# GREEN_SCH.net
KiCad netlist of a schematic drawn in Altium Designer
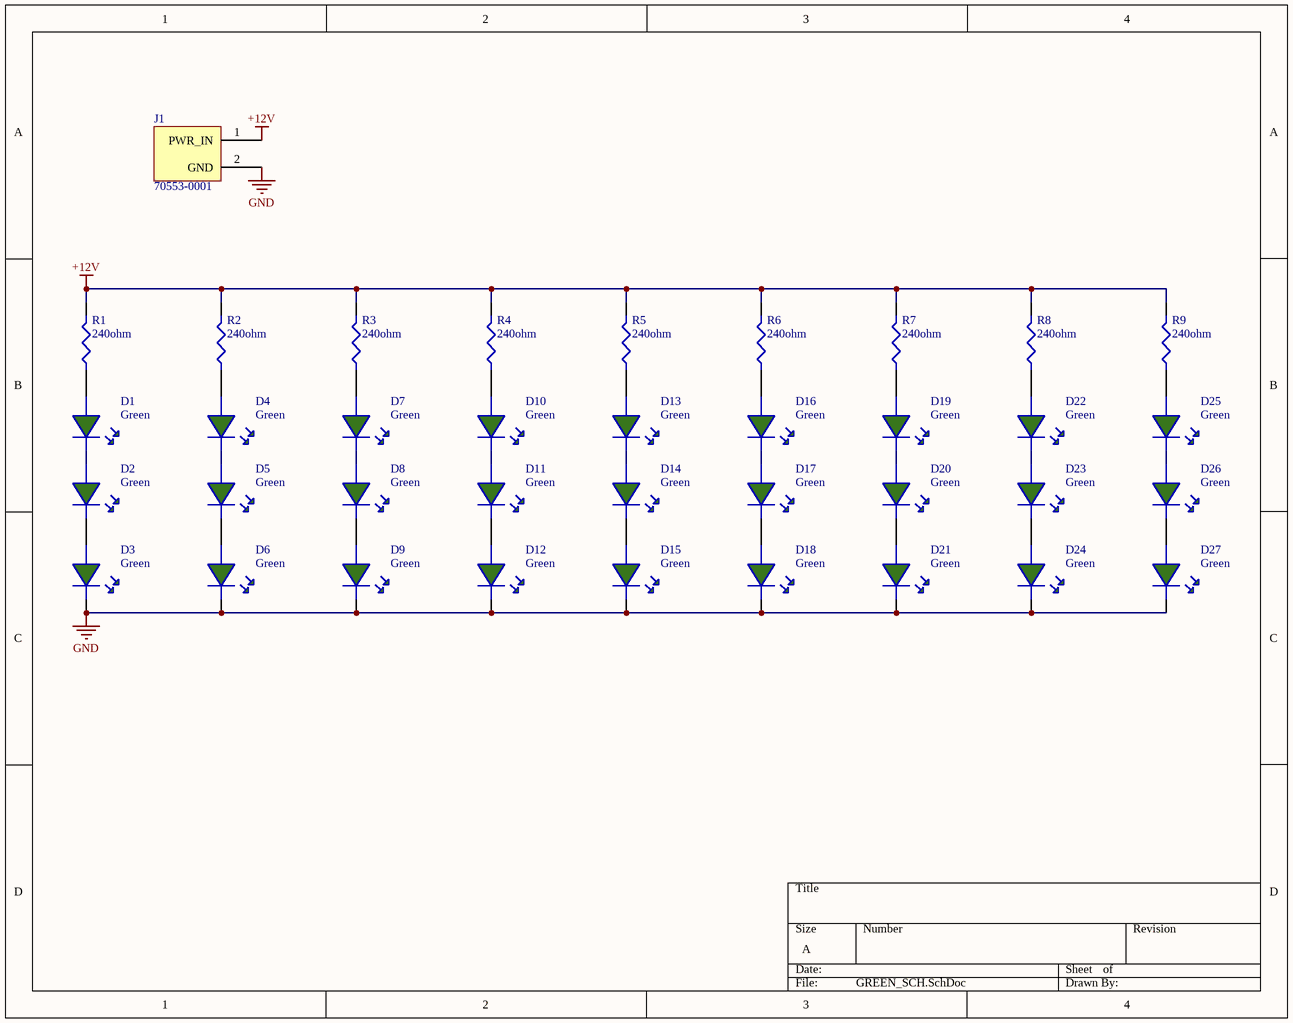
[diagram p0: GREEN_SCH.SchDoc]

(export (version "E")
  (design (tool "Eeschema 10.0.6"))
  (components
    (comp (ref "D1")
      (value "Green")
      (footprint "GREEN_LED")
      (description "LED GREEN CLEAR 0603 SMD")
      (fields (field (name "MANUFACTURER") "Inolux") (field (name "MANUFACTURER PART NUMBER") "IN-S63AT5G"))
      (libsource (lib "symbols") (part "IN-S63AT5G"))
    )
    (comp (ref "D2")
      (value "Green")
      (footprint "GREEN_LED")
      (description "LED GREEN CLEAR 0603 SMD")
      (fields (field (name "MANUFACTURER") "Inolux") (field (name "MANUFACTURER PART NUMBER") "IN-S63AT5G"))
      (libsource (lib "symbols") (part "IN-S63AT5G"))
    )
    (comp (ref "D3")
      (value "Green")
      (footprint "GREEN_LED")
      (description "LED GREEN CLEAR 0603 SMD")
      (fields (field (name "MANUFACTURER") "Inolux") (field (name "MANUFACTURER PART NUMBER") "IN-S63AT5G"))
      (libsource (lib "symbols") (part "IN-S63AT5G"))
    )
    (comp (ref "D4")
      (value "Green")
      (footprint "GREEN_LED")
      (description "LED GREEN CLEAR 0603 SMD")
      (fields (field (name "MANUFACTURER") "Inolux") (field (name "MANUFACTURER PART NUMBER") "IN-S63AT5G"))
      (libsource (lib "symbols") (part "IN-S63AT5G"))
    )
    (comp (ref "D5")
      (value "Green")
      (footprint "GREEN_LED")
      (description "LED GREEN CLEAR 0603 SMD")
      (fields (field (name "MANUFACTURER") "Inolux") (field (name "MANUFACTURER PART NUMBER") "IN-S63AT5G"))
      (libsource (lib "symbols") (part "IN-S63AT5G"))
    )
    (comp (ref "D6")
      (value "Green")
      (footprint "GREEN_LED")
      (description "LED GREEN CLEAR 0603 SMD")
      (fields (field (name "MANUFACTURER") "Inolux") (field (name "MANUFACTURER PART NUMBER") "IN-S63AT5G"))
      (libsource (lib "symbols") (part "IN-S63AT5G"))
    )
    (comp (ref "D7")
      (value "Green")
      (footprint "GREEN_LED")
      (description "LED GREEN CLEAR 0603 SMD")
      (fields (field (name "MANUFACTURER") "Inolux") (field (name "MANUFACTURER PART NUMBER") "IN-S63AT5G"))
      (libsource (lib "symbols") (part "IN-S63AT5G"))
    )
    (comp (ref "D8")
      (value "Green")
      (footprint "GREEN_LED")
      (description "LED GREEN CLEAR 0603 SMD")
      (fields (field (name "MANUFACTURER") "Inolux") (field (name "MANUFACTURER PART NUMBER") "IN-S63AT5G"))
      (libsource (lib "symbols") (part "IN-S63AT5G"))
    )
    (comp (ref "D9")
      (value "Green")
      (footprint "GREEN_LED")
      (description "LED GREEN CLEAR 0603 SMD")
      (fields (field (name "MANUFACTURER") "Inolux") (field (name "MANUFACTURER PART NUMBER") "IN-S63AT5G"))
      (libsource (lib "symbols") (part "IN-S63AT5G"))
    )
    (comp (ref "D10")
      (value "Green")
      (footprint "GREEN_LED")
      (description "LED GREEN CLEAR 0603 SMD")
      (fields (field (name "MANUFACTURER") "Inolux") (field (name "MANUFACTURER PART NUMBER") "IN-S63AT5G"))
      (libsource (lib "symbols") (part "IN-S63AT5G"))
    )
    (comp (ref "D11")
      (value "Green")
      (footprint "GREEN_LED")
      (description "LED GREEN CLEAR 0603 SMD")
      (fields (field (name "MANUFACTURER") "Inolux") (field (name "MANUFACTURER PART NUMBER") "IN-S63AT5G"))
      (libsource (lib "symbols") (part "IN-S63AT5G"))
    )
    (comp (ref "D12")
      (value "Green")
      (footprint "GREEN_LED")
      (description "LED GREEN CLEAR 0603 SMD")
      (fields (field (name "MANUFACTURER") "Inolux") (field (name "MANUFACTURER PART NUMBER") "IN-S63AT5G"))
      (libsource (lib "symbols") (part "IN-S63AT5G"))
    )
    (comp (ref "D13")
      (value "Green")
      (footprint "GREEN_LED")
      (description "LED GREEN CLEAR 0603 SMD")
      (fields (field (name "MANUFACTURER") "Inolux") (field (name "MANUFACTURER PART NUMBER") "IN-S63AT5G"))
      (libsource (lib "symbols") (part "IN-S63AT5G"))
    )
    (comp (ref "D14")
      (value "Green")
      (footprint "GREEN_LED")
      (description "LED GREEN CLEAR 0603 SMD")
      (fields (field (name "MANUFACTURER") "Inolux") (field (name "MANUFACTURER PART NUMBER") "IN-S63AT5G"))
      (libsource (lib "symbols") (part "IN-S63AT5G"))
    )
    (comp (ref "D15")
      (value "Green")
      (footprint "GREEN_LED")
      (description "LED GREEN CLEAR 0603 SMD")
      (fields (field (name "MANUFACTURER") "Inolux") (field (name "MANUFACTURER PART NUMBER") "IN-S63AT5G"))
      (libsource (lib "symbols") (part "IN-S63AT5G"))
    )
    (comp (ref "D16")
      (value "Green")
      (footprint "GREEN_LED")
      (description "LED GREEN CLEAR 0603 SMD")
      (fields (field (name "MANUFACTURER") "Inolux") (field (name "MANUFACTURER PART NUMBER") "IN-S63AT5G"))
      (libsource (lib "symbols") (part "IN-S63AT5G"))
    )
    (comp (ref "D17")
      (value "Green")
      (footprint "GREEN_LED")
      (description "LED GREEN CLEAR 0603 SMD")
      (fields (field (name "MANUFACTURER") "Inolux") (field (name "MANUFACTURER PART NUMBER") "IN-S63AT5G"))
      (libsource (lib "symbols") (part "IN-S63AT5G"))
    )
    (comp (ref "D18")
      (value "Green")
      (footprint "GREEN_LED")
      (description "LED GREEN CLEAR 0603 SMD")
      (fields (field (name "MANUFACTURER") "Inolux") (field (name "MANUFACTURER PART NUMBER") "IN-S63AT5G"))
      (libsource (lib "symbols") (part "IN-S63AT5G"))
    )
    (comp (ref "D19")
      (value "Green")
      (footprint "GREEN_LED")
      (description "LED GREEN CLEAR 0603 SMD")
      (fields (field (name "MANUFACTURER") "Inolux") (field (name "MANUFACTURER PART NUMBER") "IN-S63AT5G"))
      (libsource (lib "symbols") (part "IN-S63AT5G"))
    )
    (comp (ref "D20")
      (value "Green")
      (footprint "GREEN_LED")
      (description "LED GREEN CLEAR 0603 SMD")
      (fields (field (name "MANUFACTURER") "Inolux") (field (name "MANUFACTURER PART NUMBER") "IN-S63AT5G"))
      (libsource (lib "symbols") (part "IN-S63AT5G"))
    )
    (comp (ref "D21")
      (value "Green")
      (footprint "GREEN_LED")
      (description "LED GREEN CLEAR 0603 SMD")
      (fields (field (name "MANUFACTURER") "Inolux") (field (name "MANUFACTURER PART NUMBER") "IN-S63AT5G"))
      (libsource (lib "symbols") (part "IN-S63AT5G"))
    )
    (comp (ref "D22")
      (value "Green")
      (footprint "GREEN_LED")
      (description "LED GREEN CLEAR 0603 SMD")
      (fields (field (name "MANUFACTURER") "Inolux") (field (name "MANUFACTURER PART NUMBER") "IN-S63AT5G"))
      (libsource (lib "symbols") (part "IN-S63AT5G"))
    )
    (comp (ref "D23")
      (value "Green")
      (footprint "GREEN_LED")
      (description "LED GREEN CLEAR 0603 SMD")
      (fields (field (name "MANUFACTURER") "Inolux") (field (name "MANUFACTURER PART NUMBER") "IN-S63AT5G"))
      (libsource (lib "symbols") (part "IN-S63AT5G"))
    )
    (comp (ref "D24")
      (value "Green")
      (footprint "GREEN_LED")
      (description "LED GREEN CLEAR 0603 SMD")
      (fields (field (name "MANUFACTURER") "Inolux") (field (name "MANUFACTURER PART NUMBER") "IN-S63AT5G"))
      (libsource (lib "symbols") (part "IN-S63AT5G"))
    )
    (comp (ref "D25")
      (value "Green")
      (footprint "GREEN_LED")
      (description "LED GREEN CLEAR 0603 SMD")
      (fields (field (name "MANUFACTURER") "Inolux") (field (name "MANUFACTURER PART NUMBER") "IN-S63AT5G"))
      (libsource (lib "symbols") (part "IN-S63AT5G"))
    )
    (comp (ref "D26")
      (value "Green")
      (footprint "GREEN_LED")
      (description "LED GREEN CLEAR 0603 SMD")
      (fields (field (name "MANUFACTURER") "Inolux") (field (name "MANUFACTURER PART NUMBER") "IN-S63AT5G"))
      (libsource (lib "symbols") (part "IN-S63AT5G"))
    )
    (comp (ref "D27")
      (value "Green")
      (footprint "GREEN_LED")
      (description "LED GREEN CLEAR 0603 SMD")
      (fields (field (name "MANUFACTURER") "Inolux") (field (name "MANUFACTURER PART NUMBER") "IN-S63AT5G"))
      (libsource (lib "symbols") (part "IN-S63AT5G"))
    )
    (comp (ref "J1")
      (value "70553-0001")
      (footprint "CONNECTOR")
      (description "Headers & Wire Housings R/A HDR 2P low profile single")
      (fields (field (name "MANUFACTURER") "Molex"))
      (libsource (lib "symbols") (part "70553-0001"))
    )
    (comp (ref "R1")
      (value "240ohm")
      (footprint "RESISTOR_0805")
      (description "RES SMD 240 OHM 0.1% 1/8W 0805")
      (fields
        (field (name "MANUFACTURER") "Panasonic")
        (field (name "MANUFACTURER PART NUMBER") "ERA-6AEB241V")
      )
      (libsource (lib "symbols") (part "ERA-6AEB241V"))
    )
    (comp (ref "R2")
      (value "240ohm")
      (footprint "RESISTOR_0805")
      (description "RES SMD 240 OHM 0.1% 1/8W 0805")
      (fields
        (field (name "MANUFACTURER") "Panasonic")
        (field (name "MANUFACTURER PART NUMBER") "ERA-6AEB241V")
      )
      (libsource (lib "symbols") (part "ERA-6AEB241V"))
    )
    (comp (ref "R3")
      (value "240ohm")
      (footprint "RESISTOR_0805")
      (description "RES SMD 240 OHM 0.1% 1/8W 0805")
      (fields
        (field (name "MANUFACTURER") "Panasonic")
        (field (name "MANUFACTURER PART NUMBER") "ERA-6AEB241V")
      )
      (libsource (lib "symbols") (part "ERA-6AEB241V"))
    )
    (comp (ref "R4")
      (value "240ohm")
      (footprint "RESISTOR_0805")
      (description "RES SMD 240 OHM 0.1% 1/8W 0805")
      (fields
        (field (name "MANUFACTURER") "Panasonic")
        (field (name "MANUFACTURER PART NUMBER") "ERA-6AEB241V")
      )
      (libsource (lib "symbols") (part "ERA-6AEB241V"))
    )
    (comp (ref "R5")
      (value "240ohm")
      (footprint "RESISTOR_0805")
      (description "RES SMD 240 OHM 0.1% 1/8W 0805")
      (fields
        (field (name "MANUFACTURER") "Panasonic")
        (field (name "MANUFACTURER PART NUMBER") "ERA-6AEB241V")
      )
      (libsource (lib "symbols") (part "ERA-6AEB241V"))
    )
    (comp (ref "R6")
      (value "240ohm")
      (footprint "RESISTOR_0805")
      (description "RES SMD 240 OHM 0.1% 1/8W 0805")
      (fields
        (field (name "MANUFACTURER") "Panasonic")
        (field (name "MANUFACTURER PART NUMBER") "ERA-6AEB241V")
      )
      (libsource (lib "symbols") (part "ERA-6AEB241V"))
    )
    (comp (ref "R7")
      (value "240ohm")
      (footprint "RESISTOR_0805")
      (description "RES SMD 240 OHM 0.1% 1/8W 0805")
      (fields
        (field (name "MANUFACTURER") "Panasonic")
        (field (name "MANUFACTURER PART NUMBER") "ERA-6AEB241V")
      )
      (libsource (lib "symbols") (part "ERA-6AEB241V"))
    )
    (comp (ref "R8")
      (value "240ohm")
      (footprint "RESISTOR_0805")
      (description "RES SMD 240 OHM 0.1% 1/8W 0805")
      (fields
        (field (name "MANUFACTURER") "Panasonic")
        (field (name "MANUFACTURER PART NUMBER") "ERA-6AEB241V")
      )
      (libsource (lib "symbols") (part "ERA-6AEB241V"))
    )
    (comp (ref "R9")
      (value "240ohm")
      (footprint "RESISTOR_0805")
      (description "RES SMD 240 OHM 0.1% 1/8W 0805")
      (fields
        (field (name "MANUFACTURER") "Panasonic")
        (field (name "MANUFACTURER PART NUMBER") "ERA-6AEB241V")
      )
      (libsource (lib "symbols") (part "ERA-6AEB241V"))
    )
  )
  (nets
    (net (code "1") (name "+12V") (class "Default")
      (node (ref "J1") (pin "1") (pinfunction "PWR_IN_1") (pintype "passive"))
      (node (ref "R1") (pin "2") (pinfunction "2_2") (pintype "passive"))
      (node (ref "R2") (pin "2") (pinfunction "2_2") (pintype "passive"))
      (node (ref "R3") (pin "2") (pinfunction "2_2") (pintype "passive"))
      (node (ref "R4") (pin "2") (pinfunction "2_2") (pintype "passive"))
      (node (ref "R5") (pin "2") (pinfunction "2_2") (pintype "passive"))
      (node (ref "R6") (pin "2") (pinfunction "2_2") (pintype "passive"))
      (node (ref "R7") (pin "2") (pinfunction "2_2") (pintype "passive"))
      (node (ref "R8") (pin "2") (pinfunction "2_2") (pintype "passive"))
      (node (ref "R9") (pin "2") (pinfunction "2_2") (pintype "passive"))
    )
    (net (code "2") (name "GND") (class "Default")
      (node (ref "D12") (pin "2") (pinfunction "2_2") (pintype "passive"))
      (node (ref "D15") (pin "2") (pinfunction "2_2") (pintype "passive"))
      (node (ref "D18") (pin "2") (pinfunction "2_2") (pintype "passive"))
      (node (ref "D21") (pin "2") (pinfunction "2_2") (pintype "passive"))
      (node (ref "D24") (pin "2") (pinfunction "2_2") (pintype "passive"))
      (node (ref "D27") (pin "2") (pinfunction "2_2") (pintype "passive"))
      (node (ref "D3") (pin "2") (pinfunction "2_2") (pintype "passive"))
      (node (ref "D6") (pin "2") (pinfunction "2_2") (pintype "passive"))
      (node (ref "D9") (pin "2") (pinfunction "2_2") (pintype "passive"))
      (node (ref "J1") (pin "2") (pinfunction "GND_2") (pintype "passive"))
    )
    (net (code "3") (name "Net-(D1-Pad1)") (class "Default")
      (node (ref "D1") (pin "1") (pinfunction "1_1") (pintype "passive"))
      (node (ref "R1") (pin "1") (pinfunction "1_1") (pintype "passive"))
    )
    (net (code "4") (name "Net-(D1-Pad2)") (class "Default")
      (node (ref "D1") (pin "2") (pinfunction "2_2") (pintype "passive"))
      (node (ref "D2") (pin "1") (pinfunction "1_1") (pintype "passive"))
    )
    (net (code "5") (name "Net-(D2-Pad2)") (class "Default")
      (node (ref "D2") (pin "2") (pinfunction "2_2") (pintype "passive"))
      (node (ref "D3") (pin "1") (pinfunction "1_1") (pintype "passive"))
    )
    (net (code "6") (name "Net-(D4-Pad1)") (class "Default")
      (node (ref "D4") (pin "1") (pinfunction "1_1") (pintype "passive"))
      (node (ref "R2") (pin "1") (pinfunction "1_1") (pintype "passive"))
    )
    (net (code "7") (name "Net-(D4-Pad2)") (class "Default")
      (node (ref "D4") (pin "2") (pinfunction "2_2") (pintype "passive"))
      (node (ref "D5") (pin "1") (pinfunction "1_1") (pintype "passive"))
    )
    (net (code "8") (name "Net-(D5-Pad2)") (class "Default")
      (node (ref "D5") (pin "2") (pinfunction "2_2") (pintype "passive"))
      (node (ref "D6") (pin "1") (pinfunction "1_1") (pintype "passive"))
    )
    (net (code "9") (name "Net-(D7-Pad1)") (class "Default")
      (node (ref "D7") (pin "1") (pinfunction "1_1") (pintype "passive"))
      (node (ref "R3") (pin "1") (pinfunction "1_1") (pintype "passive"))
    )
    (net (code "10") (name "Net-(D7-Pad2)") (class "Default")
      (node (ref "D7") (pin "2") (pinfunction "2_2") (pintype "passive"))
      (node (ref "D8") (pin "1") (pinfunction "1_1") (pintype "passive"))
    )
    (net (code "11") (name "Net-(D8-Pad2)") (class "Default")
      (node (ref "D8") (pin "2") (pinfunction "2_2") (pintype "passive"))
      (node (ref "D9") (pin "1") (pinfunction "1_1") (pintype "passive"))
    )
    (net (code "12") (name "Net-(D10-Pad1)") (class "Default")
      (node (ref "D10") (pin "1") (pinfunction "1_1") (pintype "passive"))
      (node (ref "R4") (pin "1") (pinfunction "1_1") (pintype "passive"))
    )
    (net (code "13") (name "Net-(D10-Pad2)") (class "Default")
      (node (ref "D10") (pin "2") (pinfunction "2_2") (pintype "passive"))
      (node (ref "D11") (pin "1") (pinfunction "1_1") (pintype "passive"))
    )
    (net (code "14") (name "Net-(D11-Pad2)") (class "Default")
      (node (ref "D11") (pin "2") (pinfunction "2_2") (pintype "passive"))
      (node (ref "D12") (pin "1") (pinfunction "1_1") (pintype "passive"))
    )
    (net (code "15") (name "Net-(D13-Pad1)") (class "Default")
      (node (ref "D13") (pin "1") (pinfunction "1_1") (pintype "passive"))
      (node (ref "R5") (pin "1") (pinfunction "1_1") (pintype "passive"))
    )
    (net (code "16") (name "Net-(D13-Pad2)") (class "Default")
      (node (ref "D13") (pin "2") (pinfunction "2_2") (pintype "passive"))
      (node (ref "D14") (pin "1") (pinfunction "1_1") (pintype "passive"))
    )
    (net (code "17") (name "Net-(D14-Pad2)") (class "Default")
      (node (ref "D14") (pin "2") (pinfunction "2_2") (pintype "passive"))
      (node (ref "D15") (pin "1") (pinfunction "1_1") (pintype "passive"))
    )
    (net (code "18") (name "Net-(D16-Pad1)") (class "Default")
      (node (ref "D16") (pin "1") (pinfunction "1_1") (pintype "passive"))
      (node (ref "R6") (pin "1") (pinfunction "1_1") (pintype "passive"))
    )
    (net (code "19") (name "Net-(D16-Pad2)") (class "Default")
      (node (ref "D16") (pin "2") (pinfunction "2_2") (pintype "passive"))
      (node (ref "D17") (pin "1") (pinfunction "1_1") (pintype "passive"))
    )
    (net (code "20") (name "Net-(D17-Pad2)") (class "Default")
      (node (ref "D17") (pin "2") (pinfunction "2_2") (pintype "passive"))
      (node (ref "D18") (pin "1") (pinfunction "1_1") (pintype "passive"))
    )
    (net (code "21") (name "Net-(D19-Pad1)") (class "Default")
      (node (ref "D19") (pin "1") (pinfunction "1_1") (pintype "passive"))
      (node (ref "R7") (pin "1") (pinfunction "1_1") (pintype "passive"))
    )
    (net (code "22") (name "Net-(D19-Pad2)") (class "Default")
      (node (ref "D19") (pin "2") (pinfunction "2_2") (pintype "passive"))
      (node (ref "D20") (pin "1") (pinfunction "1_1") (pintype "passive"))
    )
    (net (code "23") (name "Net-(D20-Pad2)") (class "Default")
      (node (ref "D20") (pin "2") (pinfunction "2_2") (pintype "passive"))
      (node (ref "D21") (pin "1") (pinfunction "1_1") (pintype "passive"))
    )
    (net (code "24") (name "Net-(D22-Pad1)") (class "Default")
      (node (ref "D22") (pin "1") (pinfunction "1_1") (pintype "passive"))
      (node (ref "R8") (pin "1") (pinfunction "1_1") (pintype "passive"))
    )
    (net (code "25") (name "Net-(D22-Pad2)") (class "Default")
      (node (ref "D22") (pin "2") (pinfunction "2_2") (pintype "passive"))
      (node (ref "D23") (pin "1") (pinfunction "1_1") (pintype "passive"))
    )
    (net (code "26") (name "Net-(D23-Pad2)") (class "Default")
      (node (ref "D23") (pin "2") (pinfunction "2_2") (pintype "passive"))
      (node (ref "D24") (pin "1") (pinfunction "1_1") (pintype "passive"))
    )
    (net (code "27") (name "Net-(D25-Pad1)") (class "Default")
      (node (ref "D25") (pin "1") (pinfunction "1_1") (pintype "passive"))
      (node (ref "R9") (pin "1") (pinfunction "1_1") (pintype "passive"))
    )
    (net (code "28") (name "Net-(D25-Pad2)") (class "Default")
      (node (ref "D25") (pin "2") (pinfunction "2_2") (pintype "passive"))
      (node (ref "D26") (pin "1") (pinfunction "1_1") (pintype "passive"))
    )
    (net (code "29") (name "Net-(D26-Pad2)") (class "Default")
      (node (ref "D26") (pin "2") (pinfunction "2_2") (pintype "passive"))
      (node (ref "D27") (pin "1") (pinfunction "1_1") (pintype "passive"))
    )
  )
)
